# 1-WireSlavePlug.net
KiCad netlist of a schematic drawn in EAGLE
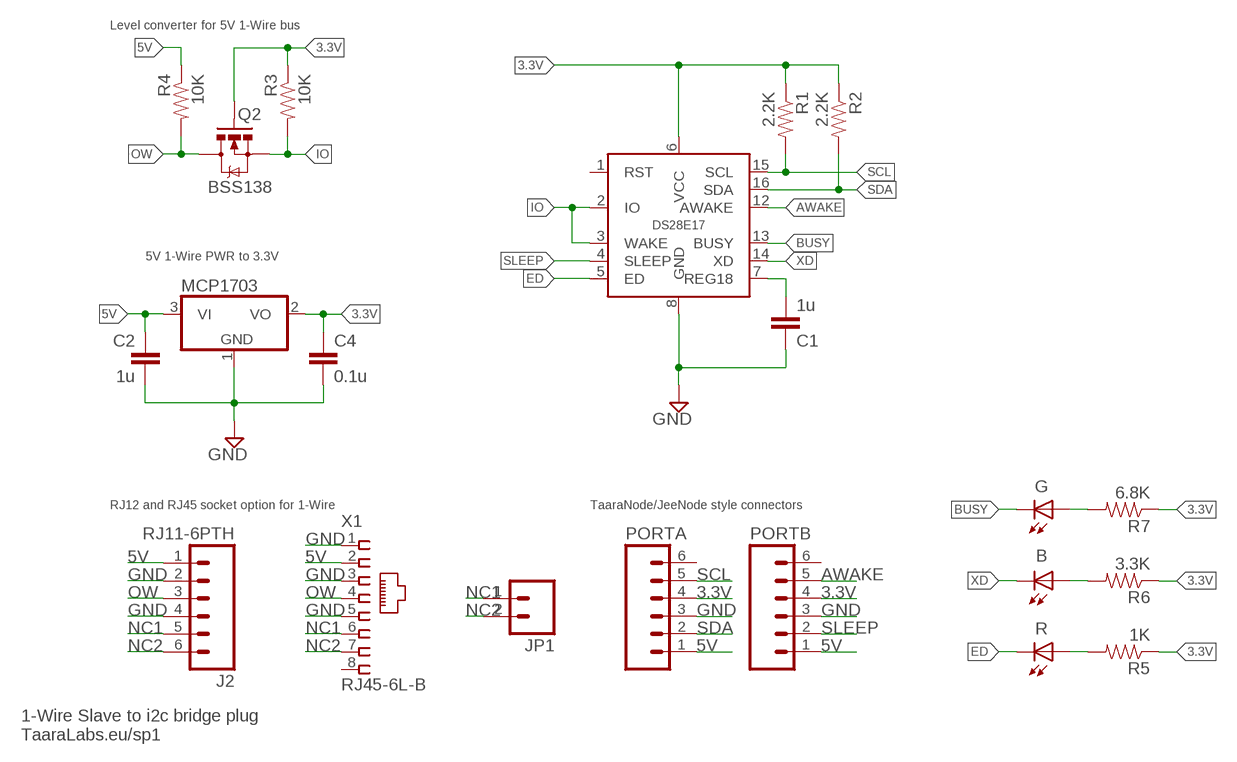
[diagram p0: schematic, sheet 1]

(export (version "E")
  (design (tool "Eeschema 10.0.6"))
  (components
    (comp (ref "C1")
      (value "1u")
      (footprint "eagle-import:0603-CAP")
      (libsource (lib "eagle-import") (part "CAP0603-CAP"))
    )
    (comp (ref "C2")
      (value "1u")
      (footprint "eagle-import:0603-CAP")
      (libsource (lib "eagle-import") (part "CAP0603-CAP"))
    )
    (comp (ref "C4")
      (value "0.1u")
      (footprint "eagle-import:0603-CAP")
      (libsource (lib "eagle-import") (part "CAP0603-CAP"))
    )
    (comp (ref "IC3")
      (value "MCP1703")
      (footprint "eagle-import:SOT23")
      (libsource (lib "eagle-import") (part "MCP1703CB"))
    )
    (comp (ref "J2")
      (value "RJ11-6PTH")
      (footprint "eagle-import:RJ11-6")
      (libsource (lib "eagle-import") (part "RJ11-6PTH"))
    )
    (comp (ref "JP1")
      (value "M02PTH")
      (footprint "eagle-import:1X02")
      (libsource (lib "eagle-import") (part "M02PTH"))
    )
    (comp (ref "LED")
      (value "R")
      (footprint "eagle-import:CHIPLED_0603")
      (libsource (lib "eagle-import") (part "LEDCHIPLED_0603"))
    )
    (comp (ref "LED1")
      (value "B")
      (footprint "eagle-import:CHIPLED_0603")
      (libsource (lib "eagle-import") (part "LEDCHIPLED_0603"))
    )
    (comp (ref "LED2")
      (value "G")
      (footprint "eagle-import:CHIPLED_0603")
      (libsource (lib "eagle-import") (part "LEDCHIPLED_0603"))
    )
    (comp (ref "PORTA")
      (value "M06SIP_LOCK")
      (footprint "eagle-import:1X06-SIP_LOCK")
      (libsource (lib "eagle-import") (part "M06SIP_LOCK"))
    )
    (comp (ref "PORTB")
      (value "M06SIP_LOCK")
      (footprint "eagle-import:1X06-SIP_LOCK")
      (libsource (lib "eagle-import") (part "M06SIP_LOCK"))
    )
    (comp (ref "Q2")
      (value "BSS138")
      (footprint "eagle-import:SOT23-3")
      (libsource (lib "eagle-import") (part "MOSFET-NCHANNELSMD"))
    )
    (comp (ref "R1")
      (value "2.2K")
      (footprint "eagle-import:0603-RES")
      (libsource (lib "eagle-import") (part "RESISTOR0603-RES"))
    )
    (comp (ref "R2")
      (value "2.2K")
      (footprint "eagle-import:0603-RES")
      (libsource (lib "eagle-import") (part "RESISTOR0603-RES"))
    )
    (comp (ref "R3")
      (value "10K")
      (footprint "eagle-import:0603-RES")
      (libsource (lib "eagle-import") (part "RESISTOR0603-RES"))
    )
    (comp (ref "R4")
      (value "10K")
      (footprint "eagle-import:0603-RES")
      (libsource (lib "eagle-import") (part "RESISTOR0603-RES"))
    )
    (comp (ref "R5")
      (value "1K")
      (footprint "eagle-import:0603-RES")
      (libsource (lib "eagle-import") (part "RESISTOR0603-RES"))
    )
    (comp (ref "R6")
      (value "3.3K")
      (footprint "eagle-import:0603-RES")
      (libsource (lib "eagle-import") (part "RESISTOR0603-RES"))
    )
    (comp (ref "R7")
      (value "6.8K")
      (footprint "eagle-import:0603-RES")
      (libsource (lib "eagle-import") (part "RESISTOR0603-RES"))
    )
    (comp (ref "U$2")
      (value "DS28E17")
      (footprint "eagle-import:TQFN-16_4X4")
      (libsource (lib "eagle-import") (part "DS28E17"))
    )
    (comp (ref "X1")
      (value "RJ45-6L-B")
      (footprint "eagle-import:RJ45-NO-SHIELD")
      (libsource (lib "eagle-import") (part "RJ45-6L-B"))
    )
  )
  (nets
    (net (code "1") (name "/NC1") (class "Default")
      (node (ref "J2") (pin "5") (pinfunction "5_5") (pintype "passive"))
      (node (ref "JP1") (pin "1") (pinfunction "1_1") (pintype "passive"))
      (node (ref "X1") (pin "6") (pinfunction "6_6") (pintype "passive"))
    )
    (net (code "2") (name "/NC2") (class "Default")
      (node (ref "J2") (pin "6") (pinfunction "6_6") (pintype "passive"))
      (node (ref "JP1") (pin "2") (pinfunction "2_2") (pintype "passive"))
      (node (ref "X1") (pin "7") (pinfunction "7_7") (pintype "passive"))
    )
    (net (code "3") (name "3.3V") (class "Default")
      (node (ref "C4") (pin "1") (pinfunction "1_1") (pintype "passive"))
      (node (ref "IC3") (pin "2") (pinfunction "VO_2") (pintype "passive"))
      (node (ref "PORTA") (pin "4") (pinfunction "4_4") (pintype "passive"))
      (node (ref "PORTB") (pin "4") (pinfunction "4_4") (pintype "passive"))
      (node (ref "Q2") (pin "1") (pinfunction "G_1") (pintype "passive"))
      (node (ref "R1") (pin "1") (pinfunction "1_1") (pintype "passive"))
      (node (ref "R2") (pin "1") (pinfunction "1_1") (pintype "passive"))
      (node (ref "R3") (pin "1") (pinfunction "1_1") (pintype "passive"))
      (node (ref "R5") (pin "1") (pinfunction "1_1") (pintype "passive"))
      (node (ref "R6") (pin "1") (pinfunction "1_1") (pintype "passive"))
      (node (ref "R7") (pin "1") (pinfunction "1_1") (pintype "passive"))
      (node (ref "U$2") (pin "6") (pinfunction "VCC_6") (pintype "power_in"))
    )
    (net (code "4") (name "5V") (class "Default")
      (node (ref "C2") (pin "1") (pinfunction "1_1") (pintype "passive"))
      (node (ref "IC3") (pin "3") (pinfunction "VI_3") (pintype "input"))
      (node (ref "J2") (pin "1") (pinfunction "1_1") (pintype "passive"))
      (node (ref "PORTA") (pin "1") (pinfunction "1_1") (pintype "passive"))
      (node (ref "PORTB") (pin "1") (pinfunction "1_1") (pintype "passive"))
      (node (ref "R4") (pin "1") (pinfunction "1_1") (pintype "passive"))
      (node (ref "X1") (pin "2") (pinfunction "2_2") (pintype "passive"))
    )
    (net (code "5") (name "AWAKE") (class "Default")
      (node (ref "PORTB") (pin "5") (pinfunction "5_5") (pintype "passive"))
      (node (ref "U$2") (pin "12") (pinfunction "AWAKE_12") (pintype "bidirectional"))
    )
    (net (code "6") (name "BUSY") (class "Default")
      (node (ref "LED2") (pin "C") (pinfunction "C_C") (pintype "passive"))
      (node (ref "U$2") (pin "13") (pinfunction "BUSY_13") (pintype "bidirectional"))
    )
    (net (code "7") (name "ED") (class "Default")
      (node (ref "LED") (pin "C") (pinfunction "C_C") (pintype "passive"))
      (node (ref "U$2") (pin "5") (pinfunction "ED_5") (pintype "bidirectional"))
    )
    (net (code "8") (name "GND") (class "Default")
      (node (ref "C1") (pin "1") (pinfunction "1_1") (pintype "passive"))
      (node (ref "C2") (pin "2") (pinfunction "2_2") (pintype "passive"))
      (node (ref "C4") (pin "2") (pinfunction "2_2") (pintype "passive"))
      (node (ref "IC3") (pin "1") (pinfunction "GND_1") (pintype "passive"))
      (node (ref "J2") (pin "2") (pinfunction "2_2") (pintype "passive"))
      (node (ref "J2") (pin "4") (pinfunction "4_4") (pintype "passive"))
      (node (ref "PORTA") (pin "3") (pinfunction "3_3") (pintype "passive"))
      (node (ref "PORTB") (pin "3") (pinfunction "3_3") (pintype "passive"))
      (node (ref "U$2") (pin "8") (pinfunction "GND_8") (pintype "power_in"))
      (node (ref "X1") (pin "1") (pinfunction "1_1") (pintype "passive"))
      (node (ref "X1") (pin "3") (pinfunction "3_3") (pintype "passive"))
      (node (ref "X1") (pin "5") (pinfunction "5_5") (pintype "passive"))
    )
    (net (code "9") (name "IO") (class "Default")
      (node (ref "Q2") (pin "2") (pinfunction "S_2") (pintype "passive"))
      (node (ref "R3") (pin "2") (pinfunction "2_2") (pintype "passive"))
      (node (ref "U$2") (pin "2") (pinfunction "IO_2") (pintype "bidirectional"))
      (node (ref "U$2") (pin "3") (pinfunction "WAKE_3") (pintype "bidirectional"))
    )
    (net (code "10") (name "Net-(LED-PadA)") (class "Default")
      (node (ref "LED") (pin "A") (pinfunction "A_A") (pintype "passive"))
      (node (ref "R5") (pin "2") (pinfunction "2_2") (pintype "passive"))
    )
    (net (code "11") (name "Net-(LED1-PadA)") (class "Default")
      (node (ref "LED1") (pin "A") (pinfunction "A_A") (pintype "passive"))
      (node (ref "R6") (pin "2") (pinfunction "2_2") (pintype "passive"))
    )
    (net (code "12") (name "Net-(LED2-PadA)") (class "Default")
      (node (ref "LED2") (pin "A") (pinfunction "A_A") (pintype "passive"))
      (node (ref "R7") (pin "2") (pinfunction "2_2") (pintype "passive"))
    )
    (net (code "13") (name "Net-(U$2-REG18)") (class "Default")
      (node (ref "C1") (pin "2") (pinfunction "2_2") (pintype "passive"))
      (node (ref "U$2") (pin "7") (pinfunction "REG18_7") (pintype "bidirectional"))
    )
    (net (code "14") (name "OW") (class "Default")
      (node (ref "J2") (pin "3") (pinfunction "3_3") (pintype "passive"))
      (node (ref "Q2") (pin "3") (pinfunction "D_3") (pintype "passive"))
      (node (ref "R4") (pin "2") (pinfunction "2_2") (pintype "passive"))
      (node (ref "X1") (pin "4") (pinfunction "4_4") (pintype "passive"))
    )
    (net (code "15") (name "SCL") (class "Default")
      (node (ref "PORTA") (pin "5") (pinfunction "5_5") (pintype "passive"))
      (node (ref "R1") (pin "2") (pinfunction "2_2") (pintype "passive"))
      (node (ref "U$2") (pin "15") (pinfunction "SCL_15") (pintype "bidirectional"))
    )
    (net (code "16") (name "SDA") (class "Default")
      (node (ref "PORTA") (pin "2") (pinfunction "2_2") (pintype "passive"))
      (node (ref "R2") (pin "2") (pinfunction "2_2") (pintype "passive"))
      (node (ref "U$2") (pin "16") (pinfunction "SDA_16") (pintype "bidirectional"))
    )
    (net (code "17") (name "SLEEP") (class "Default")
      (node (ref "PORTB") (pin "2") (pinfunction "2_2") (pintype "passive"))
      (node (ref "U$2") (pin "4") (pinfunction "SLEEP_4") (pintype "bidirectional"))
    )
    (net (code "18") (name "XD") (class "Default")
      (node (ref "LED1") (pin "C") (pinfunction "C_C") (pintype "passive"))
      (node (ref "U$2") (pin "14") (pinfunction "XD_14") (pintype "bidirectional"))
    )
    (net (code "19") (name "unconnected-(PORTA-Pad6)") (class "Default")
      (node (ref "PORTA") (pin "6") (pinfunction "6_6") (pintype "passive"))
    )
    (net (code "20") (name "unconnected-(PORTB-Pad6)") (class "Default")
      (node (ref "PORTB") (pin "6") (pinfunction "6_6") (pintype "passive"))
    )
    (net (code "21") (name "unconnected-(U$2-RST-Pad1)") (class "Default")
      (node (ref "U$2") (pin "1") (pinfunction "RST_1") (pintype "bidirectional"))
    )
    (net (code "22") (name "unconnected-(X1-Pad8)") (class "Default")
      (node (ref "X1") (pin "8") (pinfunction "8_8") (pintype "passive"))
    )
  )
)
